# 2022.net
KiCad netlist of a schematic drawn in EAGLE
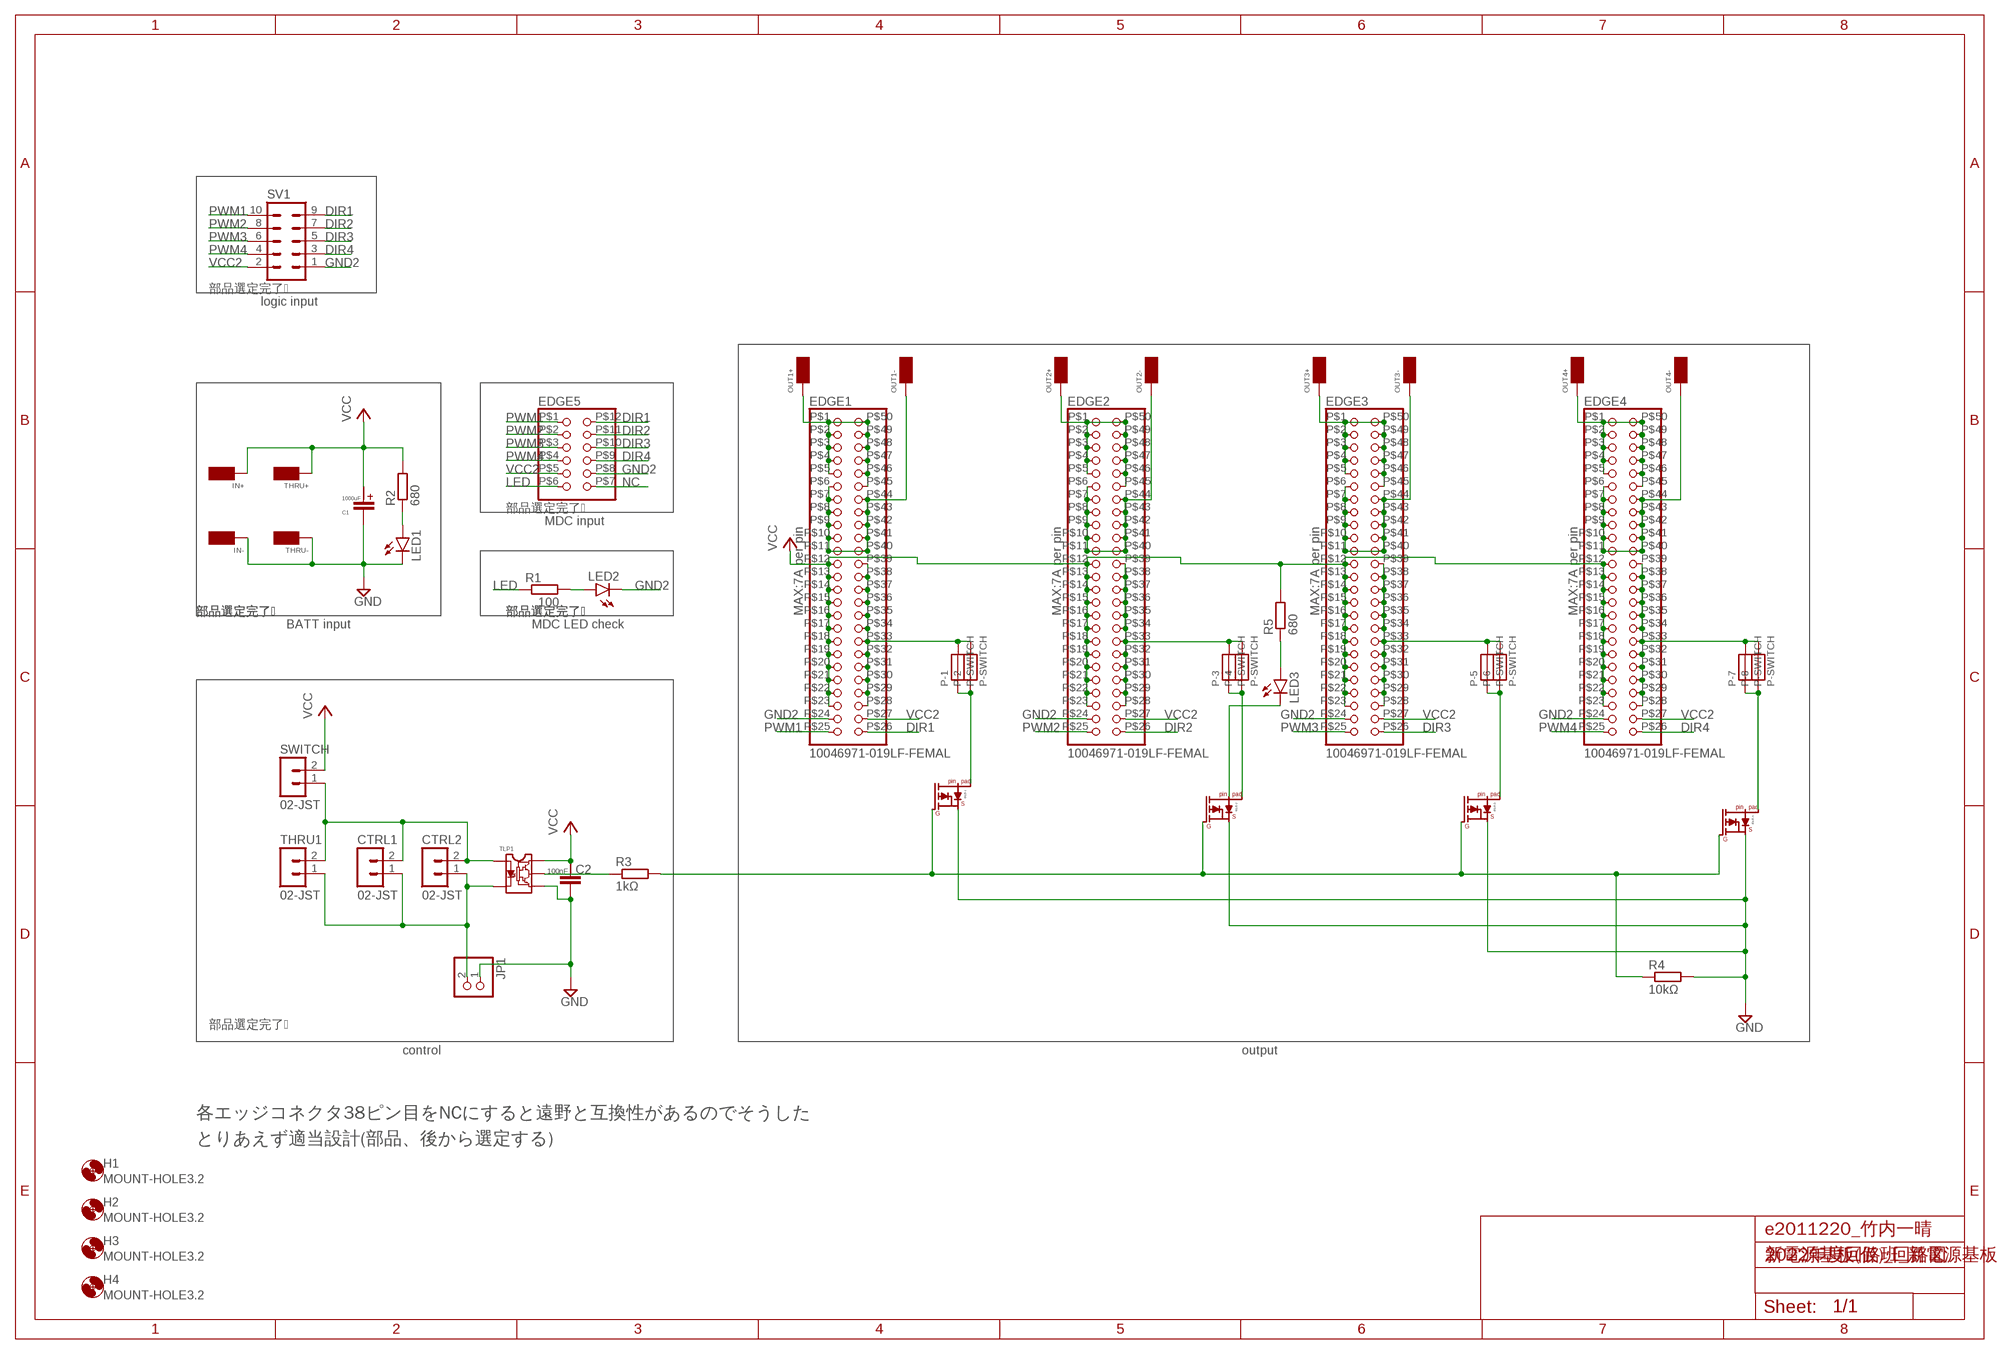
[diagram p0: schematic, sheet 1]

(export (version "E")
  (design (tool "Eeschema 10.0.6"))
  (components
    (comp (ref "C1")
      (value "50ZLH1000MEFC16X25")
      (footprint "eagle-import:50ZLH1000MEFC16X25")
      (libsource (lib "eagle-import") (part "50ZLH1000MEFC16X25"))
    )
    (comp (ref "C2")
      (value "GCM188L81H104KA57")
      (footprint "eagle-import:GCM188L81H104KA57")
      (libsource (lib "eagle-import") (part "GCM188L81H104KA57"))
    )
    (comp (ref "CTRL1")
      (value "02-JST")
      (footprint "eagle-import:B2B-XH")
      (libsource (lib "eagle-import") (part "02-JST"))
    )
    (comp (ref "CTRL2")
      (value "02-JST")
      (footprint "eagle-import:B2B-XH")
      (libsource (lib "eagle-import") (part "02-JST"))
    )
    (comp (ref "EDGE1")
      (value "10046971-019LF-FEMAL")
      (footprint "eagle-import:10046971-019LF")
      (libsource (lib "eagle-import") (part "10046971-019LF-FEMAL"))
    )
    (comp (ref "EDGE2")
      (value "10046971-019LF-FEMAL")
      (footprint "eagle-import:10046971-019LF")
      (libsource (lib "eagle-import") (part "10046971-019LF-FEMAL"))
    )
    (comp (ref "EDGE3")
      (value "10046971-019LF-FEMAL")
      (footprint "eagle-import:10046971-019LF")
      (libsource (lib "eagle-import") (part "10046971-019LF-FEMAL"))
    )
    (comp (ref "EDGE4")
      (value "10046971-019LF-FEMAL")
      (footprint "eagle-import:10046971-019LF")
      (libsource (lib "eagle-import") (part "10046971-019LF-FEMAL"))
    )
    (comp (ref "EDGE5")
      (value "7-5530843-6")
      (footprint "eagle-import:7-5530843-6")
      (libsource (lib "eagle-import") (part "7-5530843-6"))
    )
    (comp (ref "H1")
      (value "MOUNT-HOLE3.2")
      (footprint "eagle-import:3,2")
      (libsource (lib "eagle-import") (part "MOUNT-HOLE3.2"))
    )
    (comp (ref "H2")
      (value "MOUNT-HOLE3.2")
      (footprint "eagle-import:3,2")
      (libsource (lib "eagle-import") (part "MOUNT-HOLE3.2"))
    )
    (comp (ref "H3")
      (value "MOUNT-HOLE3.2")
      (footprint "eagle-import:3,2")
      (libsource (lib "eagle-import") (part "MOUNT-HOLE3.2"))
    )
    (comp (ref "H4")
      (value "MOUNT-HOLE3.2")
      (footprint "eagle-import:3,2")
      (libsource (lib "eagle-import") (part "MOUNT-HOLE3.2"))
    )
    (comp (ref "IN+")
      (value "PADS14")
      (footprint "eagle-import:AWG14")
      (libsource (lib "eagle-import") (part "PADS14"))
    )
    (comp (ref "IN-")
      (value "PADS14")
      (footprint "eagle-import:AWG14")
      (libsource (lib "eagle-import") (part "PADS14"))
    )
    (comp (ref "IRLB-1")
      (value "IRLB3813_2")
      (footprint "eagle-import:TO-220AB-PUT")
      (libsource (lib "eagle-import") (part "IRLB3813_2"))
    )
    (comp (ref "IRLB-2")
      (value "IRLB3813_2")
      (footprint "eagle-import:TO-220AB-PUT")
      (libsource (lib "eagle-import") (part "IRLB3813_2"))
    )
    (comp (ref "IRLB-3")
      (value "IRLB3813_2")
      (footprint "eagle-import:TO-220AB-PUT")
      (libsource (lib "eagle-import") (part "IRLB3813_2"))
    )
    (comp (ref "IRLB-4")
      (value "IRLB3813_2")
      (footprint "eagle-import:TO-220AB-PUT")
      (libsource (lib "eagle-import") (part "IRLB3813_2"))
    )
    (comp (ref "JP1")
      (value "PINHD-1X2")
      (footprint "eagle-import:1X02")
      (libsource (lib "eagle-import") (part "PINHD-1X2"))
    )
    (comp (ref "LED1")
      (value "LED5MM")
      (footprint "eagle-import:LED5MM")
      (libsource (lib "eagle-import") (part "LED5MM"))
    )
    (comp (ref "LED2")
      (value "LED5MM")
      (footprint "eagle-import:LED5MM")
      (libsource (lib "eagle-import") (part "LED5MM"))
    )
    (comp (ref "LED3")
      (value "LED5MM")
      (footprint "eagle-import:LED5MM")
      (libsource (lib "eagle-import") (part "LED5MM"))
    )
    (comp (ref "OUT1+")
      (value "PADS14")
      (footprint "eagle-import:AWG14")
      (libsource (lib "eagle-import") (part "PADS14"))
    )
    (comp (ref "OUT1-")
      (value "PADS14")
      (footprint "eagle-import:AWG14")
      (libsource (lib "eagle-import") (part "PADS14"))
    )
    (comp (ref "OUT2+")
      (value "PADS14")
      (footprint "eagle-import:AWG14")
      (libsource (lib "eagle-import") (part "PADS14"))
    )
    (comp (ref "OUT2-")
      (value "PADS14")
      (footprint "eagle-import:AWG14")
      (libsource (lib "eagle-import") (part "PADS14"))
    )
    (comp (ref "OUT3+")
      (value "PADS14")
      (footprint "eagle-import:AWG14")
      (libsource (lib "eagle-import") (part "PADS14"))
    )
    (comp (ref "OUT3-")
      (value "PADS14")
      (footprint "eagle-import:AWG14")
      (libsource (lib "eagle-import") (part "PADS14"))
    )
    (comp (ref "OUT4+")
      (value "PADS14")
      (footprint "eagle-import:AWG14")
      (libsource (lib "eagle-import") (part "PADS14"))
    )
    (comp (ref "OUT4-")
      (value "PADS14")
      (footprint "eagle-import:AWG14")
      (libsource (lib "eagle-import") (part "PADS14"))
    )
    (comp (ref "P-1")
      (value "P-SWITCH")
      (footprint "eagle-import:P-SWITCH")
      (libsource (lib "eagle-import") (part "P-SWITCH"))
    )
    (comp (ref "P-2")
      (value "P-SWITCH")
      (footprint "eagle-import:P-SWITCH")
      (libsource (lib "eagle-import") (part "P-SWITCH"))
    )
    (comp (ref "P-3")
      (value "P-SWITCH")
      (footprint "eagle-import:P-SWITCH")
      (libsource (lib "eagle-import") (part "P-SWITCH"))
    )
    (comp (ref "P-4")
      (value "P-SWITCH")
      (footprint "eagle-import:P-SWITCH")
      (libsource (lib "eagle-import") (part "P-SWITCH"))
    )
    (comp (ref "P-5")
      (value "P-SWITCH")
      (footprint "eagle-import:P-SWITCH")
      (libsource (lib "eagle-import") (part "P-SWITCH"))
    )
    (comp (ref "P-6")
      (value "P-SWITCH")
      (footprint "eagle-import:P-SWITCH")
      (libsource (lib "eagle-import") (part "P-SWITCH"))
    )
    (comp (ref "P-7")
      (value "P-SWITCH")
      (footprint "eagle-import:P-SWITCH")
      (libsource (lib "eagle-import") (part "P-SWITCH"))
    )
    (comp (ref "P-8")
      (value "P-SWITCH")
      (footprint "eagle-import:P-SWITCH")
      (libsource (lib "eagle-import") (part "P-SWITCH"))
    )
    (comp (ref "R1")
      (value "100")
      (footprint "eagle-import:0204_7")
      (libsource (lib "eagle-import") (part "R-EU_0204/7"))
    )
    (comp (ref "R2")
      (value "680")
      (footprint "eagle-import:0204_7")
      (libsource (lib "eagle-import") (part "R-EU_0204/7"))
    )
    (comp (ref "R3")
      (value "1kΩ")
      (footprint "eagle-import:0204_7")
      (libsource (lib "eagle-import") (part "R-EU_0204/7"))
    )
    (comp (ref "R4")
      (value "10kΩ")
      (footprint "eagle-import:0204_7")
      (libsource (lib "eagle-import") (part "R-EU_0204/7"))
    )
    (comp (ref "R5")
      (value "680")
      (footprint "eagle-import:0204_7")
      (libsource (lib "eagle-import") (part "R-EU_0204/7"))
    )
    (comp (ref "SV1")
      (value "ML10")
      (footprint "eagle-import:ML10")
      (libsource (lib "eagle-import") (part "ML10"))
    )
    (comp (ref "SWITCH")
      (value "02-JST")
      (footprint "eagle-import:B2B-XH")
      (libsource (lib "eagle-import") (part "02-JST"))
    )
    (comp (ref "THRU+")
      (value "PADS14")
      (footprint "eagle-import:AWG14")
      (libsource (lib "eagle-import") (part "PADS14"))
    )
    (comp (ref "THRU-")
      (value "PADS14")
      (footprint "eagle-import:AWG14")
      (libsource (lib "eagle-import") (part "PADS14"))
    )
    (comp (ref "THRU1")
      (value "02-JST")
      (footprint "eagle-import:B2B-XH")
      (libsource (lib "eagle-import") (part "02-JST"))
    )
    (comp (ref "TLP1")
      (value "2227MC-08-03")
      (footprint "eagle-import:2227MC-08-03")
      (libsource (lib "eagle-import") (part "2227MC-08-03"))
    )
  )
  (nets
    (net (code "1") (name "/DIR1") (class "Default")
      (node (ref "EDGE1") (pin "P$26") (pinfunction "P26_P$26") (pintype "passive"))
      (node (ref "EDGE5") (pin "P$12") (pinfunction "P12_P$12") (pintype "passive"))
      (node (ref "SV1") (pin "9") (pinfunction "9_9") (pintype "passive"))
    )
    (net (code "2") (name "/DIR2") (class "Default")
      (node (ref "EDGE2") (pin "P$26") (pinfunction "P26_P$26") (pintype "passive"))
      (node (ref "EDGE5") (pin "P$11") (pinfunction "P11_P$11") (pintype "passive"))
      (node (ref "SV1") (pin "7") (pinfunction "7_7") (pintype "passive"))
    )
    (net (code "3") (name "/DIR3") (class "Default")
      (node (ref "EDGE3") (pin "P$26") (pinfunction "P26_P$26") (pintype "passive"))
      (node (ref "EDGE5") (pin "P$10") (pinfunction "P10_P$10") (pintype "passive"))
      (node (ref "SV1") (pin "5") (pinfunction "5_5") (pintype "passive"))
    )
    (net (code "4") (name "/DIR4") (class "Default")
      (node (ref "EDGE4") (pin "P$26") (pinfunction "P26_P$26") (pintype "passive"))
      (node (ref "EDGE5") (pin "P$9") (pinfunction "P9_P$9") (pintype "passive"))
      (node (ref "SV1") (pin "3") (pinfunction "3_3") (pintype "passive"))
    )
    (net (code "5") (name "/GND2") (class "Default")
      (node (ref "EDGE1") (pin "P$24") (pinfunction "P24_P$24") (pintype "passive"))
      (node (ref "EDGE2") (pin "P$24") (pinfunction "P24_P$24") (pintype "passive"))
      (node (ref "EDGE3") (pin "P$24") (pinfunction "P24_P$24") (pintype "passive"))
      (node (ref "EDGE4") (pin "P$24") (pinfunction "P24_P$24") (pintype "passive"))
      (node (ref "EDGE5") (pin "P$8") (pinfunction "P8_P$8") (pintype "passive"))
      (node (ref "LED2") (pin "K") (pinfunction "C_K") (pintype "passive"))
      (node (ref "SV1") (pin "1") (pinfunction "1_1") (pintype "passive"))
    )
    (net (code "6") (name "/LED") (class "Default")
      (node (ref "EDGE5") (pin "P$6") (pinfunction "P6_P$6") (pintype "passive"))
      (node (ref "R1") (pin "1") (pinfunction "1_1") (pintype "passive"))
    )
    (net (code "7") (name "/NC") (class "Default")
      (node (ref "EDGE5") (pin "P$7") (pinfunction "P7_P$7") (pintype "passive"))
    )
    (net (code "8") (name "/PWM1") (class "Default")
      (node (ref "EDGE1") (pin "P$25") (pinfunction "P25_P$25") (pintype "passive"))
      (node (ref "EDGE5") (pin "P$1") (pinfunction "P1_P$1") (pintype "passive"))
      (node (ref "SV1") (pin "10") (pinfunction "10_10") (pintype "passive"))
    )
    (net (code "9") (name "/PWM2") (class "Default")
      (node (ref "EDGE2") (pin "P$25") (pinfunction "P25_P$25") (pintype "passive"))
      (node (ref "EDGE5") (pin "P$2") (pinfunction "P2_P$2") (pintype "passive"))
      (node (ref "SV1") (pin "8") (pinfunction "8_8") (pintype "passive"))
    )
    (net (code "10") (name "/PWM3") (class "Default")
      (node (ref "EDGE3") (pin "P$25") (pinfunction "P25_P$25") (pintype "passive"))
      (node (ref "EDGE5") (pin "P$3") (pinfunction "P3_P$3") (pintype "passive"))
      (node (ref "SV1") (pin "6") (pinfunction "6_6") (pintype "passive"))
    )
    (net (code "11") (name "/PWM4") (class "Default")
      (node (ref "EDGE4") (pin "P$25") (pinfunction "P25_P$25") (pintype "passive"))
      (node (ref "EDGE5") (pin "P$4") (pinfunction "P4_P$4") (pintype "passive"))
      (node (ref "SV1") (pin "4") (pinfunction "4_4") (pintype "passive"))
    )
    (net (code "12") (name "/VCC2") (class "Default")
      (node (ref "EDGE1") (pin "P$27") (pinfunction "P27_P$27") (pintype "passive"))
      (node (ref "EDGE2") (pin "P$27") (pinfunction "P27_P$27") (pintype "passive"))
      (node (ref "EDGE3") (pin "P$27") (pinfunction "P27_P$27") (pintype "passive"))
      (node (ref "EDGE4") (pin "P$27") (pinfunction "P27_P$27") (pintype "passive"))
      (node (ref "EDGE5") (pin "P$5") (pinfunction "P5_P$5") (pintype "passive"))
      (node (ref "SV1") (pin "2") (pinfunction "2_2") (pintype "passive"))
    )
    (net (code "13") (name "GND") (class "Default")
      (node (ref "C1") (pin "C") (pinfunction "CATHODE_C") (pintype "bidirectional"))
      (node (ref "C2") (pin "P$2") (pinfunction "P$2_P$2") (pintype "bidirectional"))
      (node (ref "IN-") (pin "P$1") (pinfunction "P$1_P$1") (pintype "passive"))
      (node (ref "IRLB-1") (pin "S") (pinfunction "S_S") (pintype "passive"))
      (node (ref "IRLB-2") (pin "S") (pinfunction "S_S") (pintype "passive"))
      (node (ref "IRLB-3") (pin "S") (pinfunction "S_S") (pintype "passive"))
      (node (ref "IRLB-4") (pin "S") (pinfunction "S_S") (pintype "passive"))
      (node (ref "JP1") (pin "1") (pinfunction "1_1") (pintype "passive"))
      (node (ref "LED1") (pin "K") (pinfunction "C_K") (pintype "passive"))
      (node (ref "R4") (pin "2") (pinfunction "2_2") (pintype "passive"))
      (node (ref "THRU-") (pin "P$1") (pinfunction "P$1_P$1") (pintype "passive"))
      (node (ref "TLP1") (pin "P$5") (pinfunction "GND_P$5") (pintype "passive"))
    )
    (net (code "14") (name "Net-(EDGE1-P1)") (class "Default")
      (node (ref "EDGE1") (pin "P$1") (pinfunction "P1_P$1") (pintype "passive"))
      (node (ref "EDGE1") (pin "P$2") (pinfunction "P2_P$2") (pintype "passive"))
      (node (ref "EDGE1") (pin "P$3") (pinfunction "P3_P$3") (pintype "passive"))
      (node (ref "EDGE1") (pin "P$4") (pinfunction "P4_P$4") (pintype "passive"))
      (node (ref "EDGE1") (pin "P$45") (pinfunction "P45_P$45") (pintype "passive"))
      (node (ref "EDGE1") (pin "P$46") (pinfunction "P46_P$46") (pintype "passive"))
      (node (ref "EDGE1") (pin "P$47") (pinfunction "P47_P$47") (pintype "passive"))
      (node (ref "EDGE1") (pin "P$48") (pinfunction "P48_P$48") (pintype "passive"))
      (node (ref "EDGE1") (pin "P$49") (pinfunction "P49_P$49") (pintype "passive"))
      (node (ref "EDGE1") (pin "P$5") (pinfunction "P5_P$5") (pintype "passive"))
      (node (ref "EDGE1") (pin "P$50") (pinfunction "P50_P$50") (pintype "passive"))
      (node (ref "OUT1+") (pin "P$1") (pinfunction "P$1_P$1") (pintype "passive"))
    )
    (net (code "15") (name "Net-(EDGE1-P10)") (class "Default")
      (node (ref "EDGE1") (pin "P$10") (pinfunction "P10_P$10") (pintype "passive"))
      (node (ref "EDGE1") (pin "P$11") (pinfunction "P11_P$11") (pintype "passive"))
      (node (ref "EDGE1") (pin "P$40") (pinfunction "P40_P$40") (pintype "passive"))
      (node (ref "EDGE1") (pin "P$41") (pinfunction "P41_P$41") (pintype "passive"))
      (node (ref "EDGE1") (pin "P$42") (pinfunction "P42_P$42") (pintype "passive"))
      (node (ref "EDGE1") (pin "P$43") (pinfunction "P43_P$43") (pintype "passive"))
      (node (ref "EDGE1") (pin "P$44") (pinfunction "P44_P$44") (pintype "passive"))
      (node (ref "EDGE1") (pin "P$6") (pinfunction "P6_P$6") (pintype "passive"))
      (node (ref "EDGE1") (pin "P$7") (pinfunction "P7_P$7") (pintype "passive"))
      (node (ref "EDGE1") (pin "P$8") (pinfunction "P8_P$8") (pintype "passive"))
      (node (ref "EDGE1") (pin "P$9") (pinfunction "P9_P$9") (pintype "passive"))
      (node (ref "OUT1-") (pin "P$1") (pinfunction "P$1_P$1") (pintype "passive"))
    )
    (net (code "16") (name "Net-(EDGE1-P28)") (class "Default")
      (node (ref "EDGE1") (pin "P$28") (pinfunction "P28_P$28") (pintype "passive"))
      (node (ref "EDGE1") (pin "P$29") (pinfunction "P29_P$29") (pintype "passive"))
      (node (ref "EDGE1") (pin "P$30") (pinfunction "P30_P$30") (pintype "passive"))
      (node (ref "EDGE1") (pin "P$31") (pinfunction "P31_P$31") (pintype "passive"))
      (node (ref "EDGE1") (pin "P$32") (pinfunction "P32_P$32") (pintype "passive"))
      (node (ref "EDGE1") (pin "P$33") (pinfunction "P33_P$33") (pintype "passive"))
      (node (ref "EDGE1") (pin "P$34") (pinfunction "P34_P$34") (pintype "passive"))
      (node (ref "EDGE1") (pin "P$35") (pinfunction "P35_P$35") (pintype "passive"))
      (node (ref "EDGE1") (pin "P$36") (pinfunction "P36_P$36") (pintype "passive"))
      (node (ref "EDGE1") (pin "P$37") (pinfunction "P37_P$37") (pintype "passive"))
      (node (ref "EDGE1") (pin "P$38") (pinfunction "P38_P$38") (pintype "passive"))
      (node (ref "EDGE1") (pin "P$39") (pinfunction "P39_P$39") (pintype "passive"))
      (node (ref "P-1") (pin "P$1") (pinfunction "P$1_P$1") (pintype "passive"))
      (node (ref "P-2") (pin "P$1") (pinfunction "P$1_P$1") (pintype "passive"))
    )
    (net (code "17") (name "Net-(EDGE2-P1)") (class "Default")
      (node (ref "EDGE2") (pin "P$1") (pinfunction "P1_P$1") (pintype "passive"))
      (node (ref "EDGE2") (pin "P$2") (pinfunction "P2_P$2") (pintype "passive"))
      (node (ref "EDGE2") (pin "P$3") (pinfunction "P3_P$3") (pintype "passive"))
      (node (ref "EDGE2") (pin "P$4") (pinfunction "P4_P$4") (pintype "passive"))
      (node (ref "EDGE2") (pin "P$45") (pinfunction "P45_P$45") (pintype "passive"))
      (node (ref "EDGE2") (pin "P$46") (pinfunction "P46_P$46") (pintype "passive"))
      (node (ref "EDGE2") (pin "P$47") (pinfunction "P47_P$47") (pintype "passive"))
      (node (ref "EDGE2") (pin "P$48") (pinfunction "P48_P$48") (pintype "passive"))
      (node (ref "EDGE2") (pin "P$49") (pinfunction "P49_P$49") (pintype "passive"))
      (node (ref "EDGE2") (pin "P$5") (pinfunction "P5_P$5") (pintype "passive"))
      (node (ref "EDGE2") (pin "P$50") (pinfunction "P50_P$50") (pintype "passive"))
      (node (ref "OUT2+") (pin "P$1") (pinfunction "P$1_P$1") (pintype "passive"))
    )
    (net (code "18") (name "Net-(EDGE2-P10)") (class "Default")
      (node (ref "EDGE2") (pin "P$10") (pinfunction "P10_P$10") (pintype "passive"))
      (node (ref "EDGE2") (pin "P$11") (pinfunction "P11_P$11") (pintype "passive"))
      (node (ref "EDGE2") (pin "P$40") (pinfunction "P40_P$40") (pintype "passive"))
      (node (ref "EDGE2") (pin "P$41") (pinfunction "P41_P$41") (pintype "passive"))
      (node (ref "EDGE2") (pin "P$42") (pinfunction "P42_P$42") (pintype "passive"))
      (node (ref "EDGE2") (pin "P$43") (pinfunction "P43_P$43") (pintype "passive"))
      (node (ref "EDGE2") (pin "P$44") (pinfunction "P44_P$44") (pintype "passive"))
      (node (ref "EDGE2") (pin "P$6") (pinfunction "P6_P$6") (pintype "passive"))
      (node (ref "EDGE2") (pin "P$7") (pinfunction "P7_P$7") (pintype "passive"))
      (node (ref "EDGE2") (pin "P$8") (pinfunction "P8_P$8") (pintype "passive"))
      (node (ref "EDGE2") (pin "P$9") (pinfunction "P9_P$9") (pintype "passive"))
      (node (ref "OUT2-") (pin "P$1") (pinfunction "P$1_P$1") (pintype "passive"))
    )
    (net (code "19") (name "Net-(EDGE2-P28)") (class "Default")
      (node (ref "EDGE2") (pin "P$28") (pinfunction "P28_P$28") (pintype "passive"))
      (node (ref "EDGE2") (pin "P$29") (pinfunction "P29_P$29") (pintype "passive"))
      (node (ref "EDGE2") (pin "P$30") (pinfunction "P30_P$30") (pintype "passive"))
      (node (ref "EDGE2") (pin "P$31") (pinfunction "P31_P$31") (pintype "passive"))
      (node (ref "EDGE2") (pin "P$32") (pinfunction "P32_P$32") (pintype "passive"))
      (node (ref "EDGE2") (pin "P$33") (pinfunction "P33_P$33") (pintype "passive"))
      (node (ref "EDGE2") (pin "P$34") (pinfunction "P34_P$34") (pintype "passive"))
      (node (ref "EDGE2") (pin "P$35") (pinfunction "P35_P$35") (pintype "passive"))
      (node (ref "EDGE2") (pin "P$36") (pinfunction "P36_P$36") (pintype "passive"))
      (node (ref "EDGE2") (pin "P$37") (pinfunction "P37_P$37") (pintype "passive"))
      (node (ref "EDGE2") (pin "P$38") (pinfunction "P38_P$38") (pintype "passive"))
      (node (ref "EDGE2") (pin "P$39") (pinfunction "P39_P$39") (pintype "passive"))
      (node (ref "P-3") (pin "P$1") (pinfunction "P$1_P$1") (pintype "passive"))
      (node (ref "P-4") (pin "P$1") (pinfunction "P$1_P$1") (pintype "passive"))
    )
    (net (code "20") (name "Net-(EDGE3-P1)") (class "Default")
      (node (ref "EDGE3") (pin "P$1") (pinfunction "P1_P$1") (pintype "passive"))
      (node (ref "EDGE3") (pin "P$2") (pinfunction "P2_P$2") (pintype "passive"))
      (node (ref "EDGE3") (pin "P$3") (pinfunction "P3_P$3") (pintype "passive"))
      (node (ref "EDGE3") (pin "P$4") (pinfunction "P4_P$4") (pintype "passive"))
      (node (ref "EDGE3") (pin "P$45") (pinfunction "P45_P$45") (pintype "passive"))
      (node (ref "EDGE3") (pin "P$46") (pinfunction "P46_P$46") (pintype "passive"))
      (node (ref "EDGE3") (pin "P$47") (pinfunction "P47_P$47") (pintype "passive"))
      (node (ref "EDGE3") (pin "P$48") (pinfunction "P48_P$48") (pintype "passive"))
      (node (ref "EDGE3") (pin "P$49") (pinfunction "P49_P$49") (pintype "passive"))
      (node (ref "EDGE3") (pin "P$5") (pinfunction "P5_P$5") (pintype "passive"))
      (node (ref "EDGE3") (pin "P$50") (pinfunction "P50_P$50") (pintype "passive"))
      (node (ref "OUT3+") (pin "P$1") (pinfunction "P$1_P$1") (pintype "passive"))
    )
    (net (code "21") (name "Net-(EDGE3-P10)") (class "Default")
      (node (ref "EDGE3") (pin "P$10") (pinfunction "P10_P$10") (pintype "passive"))
      (node (ref "EDGE3") (pin "P$11") (pinfunction "P11_P$11") (pintype "passive"))
      (node (ref "EDGE3") (pin "P$40") (pinfunction "P40_P$40") (pintype "passive"))
      (node (ref "EDGE3") (pin "P$41") (pinfunction "P41_P$41") (pintype "passive"))
      (node (ref "EDGE3") (pin "P$42") (pinfunction "P42_P$42") (pintype "passive"))
      (node (ref "EDGE3") (pin "P$43") (pinfunction "P43_P$43") (pintype "passive"))
      (node (ref "EDGE3") (pin "P$44") (pinfunction "P44_P$44") (pintype "passive"))
      (node (ref "EDGE3") (pin "P$6") (pinfunction "P6_P$6") (pintype "passive"))
      (node (ref "EDGE3") (pin "P$7") (pinfunction "P7_P$7") (pintype "passive"))
      (node (ref "EDGE3") (pin "P$8") (pinfunction "P8_P$8") (pintype "passive"))
      (node (ref "EDGE3") (pin "P$9") (pinfunction "P9_P$9") (pintype "passive"))
      (node (ref "OUT3-") (pin "P$1") (pinfunction "P$1_P$1") (pintype "passive"))
    )
    (net (code "22") (name "Net-(EDGE3-P28)") (class "Default")
      (node (ref "EDGE3") (pin "P$28") (pinfunction "P28_P$28") (pintype "passive"))
      (node (ref "EDGE3") (pin "P$29") (pinfunction "P29_P$29") (pintype "passive"))
      (node (ref "EDGE3") (pin "P$30") (pinfunction "P30_P$30") (pintype "passive"))
      (node (ref "EDGE3") (pin "P$31") (pinfunction "P31_P$31") (pintype "passive"))
      (node (ref "EDGE3") (pin "P$32") (pinfunction "P32_P$32") (pintype "passive"))
      (node (ref "EDGE3") (pin "P$33") (pinfunction "P33_P$33") (pintype "passive"))
      (node (ref "EDGE3") (pin "P$34") (pinfunction "P34_P$34") (pintype "passive"))
      (node (ref "EDGE3") (pin "P$35") (pinfunction "P35_P$35") (pintype "passive"))
      (node (ref "EDGE3") (pin "P$36") (pinfunction "P36_P$36") (pintype "passive"))
      (node (ref "EDGE3") (pin "P$37") (pinfunction "P37_P$37") (pintype "passive"))
      (node (ref "EDGE3") (pin "P$38") (pinfunction "P38_P$38") (pintype "passive"))
      (node (ref "EDGE3") (pin "P$39") (pinfunction "P39_P$39") (pintype "passive"))
      (node (ref "P-5") (pin "P$1") (pinfunction "P$1_P$1") (pintype "passive"))
      (node (ref "P-6") (pin "P$1") (pinfunction "P$1_P$1") (pintype "passive"))
    )
    (net (code "23") (name "Net-(EDGE4-P1)") (class "Default")
      (node (ref "EDGE4") (pin "P$1") (pinfunction "P1_P$1") (pintype "passive"))
      (node (ref "EDGE4") (pin "P$2") (pinfunction "P2_P$2") (pintype "passive"))
      (node (ref "EDGE4") (pin "P$3") (pinfunction "P3_P$3") (pintype "passive"))
      (node (ref "EDGE4") (pin "P$4") (pinfunction "P4_P$4") (pintype "passive"))
      (node (ref "EDGE4") (pin "P$45") (pinfunction "P45_P$45") (pintype "passive"))
      (node (ref "EDGE4") (pin "P$46") (pinfunction "P46_P$46") (pintype "passive"))
      (node (ref "EDGE4") (pin "P$47") (pinfunction "P47_P$47") (pintype "passive"))
      (node (ref "EDGE4") (pin "P$48") (pinfunction "P48_P$48") (pintype "passive"))
      (node (ref "EDGE4") (pin "P$49") (pinfunction "P49_P$49") (pintype "passive"))
      (node (ref "EDGE4") (pin "P$5") (pinfunction "P5_P$5") (pintype "passive"))
      (node (ref "EDGE4") (pin "P$50") (pinfunction "P50_P$50") (pintype "passive"))
      (node (ref "OUT4+") (pin "P$1") (pinfunction "P$1_P$1") (pintype "passive"))
    )
    (net (code "24") (name "Net-(EDGE4-P10)") (class "Default")
      (node (ref "EDGE4") (pin "P$10") (pinfunction "P10_P$10") (pintype "passive"))
      (node (ref "EDGE4") (pin "P$11") (pinfunction "P11_P$11") (pintype "passive"))
      (node (ref "EDGE4") (pin "P$40") (pinfunction "P40_P$40") (pintype "passive"))
      (node (ref "EDGE4") (pin "P$41") (pinfunction "P41_P$41") (pintype "passive"))
      (node (ref "EDGE4") (pin "P$42") (pinfunction "P42_P$42") (pintype "passive"))
      (node (ref "EDGE4") (pin "P$43") (pinfunction "P43_P$43") (pintype "passive"))
      (node (ref "EDGE4") (pin "P$44") (pinfunction "P44_P$44") (pintype "passive"))
      (node (ref "EDGE4") (pin "P$6") (pinfunction "P6_P$6") (pintype "passive"))
      (node (ref "EDGE4") (pin "P$7") (pinfunction "P7_P$7") (pintype "passive"))
      (node (ref "EDGE4") (pin "P$8") (pinfunction "P8_P$8") (pintype "passive"))
      (node (ref "EDGE4") (pin "P$9") (pinfunction "P9_P$9") (pintype "passive"))
      (node (ref "OUT4-") (pin "P$1") (pinfunction "P$1_P$1") (pintype "passive"))
    )
    (net (code "25") (name "Net-(EDGE4-P28)") (class "Default")
      (node (ref "EDGE4") (pin "P$28") (pinfunction "P28_P$28") (pintype "passive"))
      (node (ref "EDGE4") (pin "P$29") (pinfunction "P29_P$29") (pintype "passive"))
      (node (ref "EDGE4") (pin "P$30") (pinfunction "P30_P$30") (pintype "passive"))
      (node (ref "EDGE4") (pin "P$31") (pinfunction "P31_P$31") (pintype "passive"))
      (node (ref "EDGE4") (pin "P$32") (pinfunction "P32_P$32") (pintype "passive"))
      (node (ref "EDGE4") (pin "P$33") (pinfunction "P33_P$33") (pintype "passive"))
      (node (ref "EDGE4") (pin "P$34") (pinfunction "P34_P$34") (pintype "passive"))
      (node (ref "EDGE4") (pin "P$35") (pinfunction "P35_P$35") (pintype "passive"))
      (node (ref "EDGE4") (pin "P$36") (pinfunction "P36_P$36") (pintype "passive"))
      (node (ref "EDGE4") (pin "P$37") (pinfunction "P37_P$37") (pintype "passive"))
      (node (ref "EDGE4") (pin "P$38") (pinfunction "P38_P$38") (pintype "passive"))
      (node (ref "EDGE4") (pin "P$39") (pinfunction "P39_P$39") (pintype "passive"))
      (node (ref "P-7") (pin "P$1") (pinfunction "P$1_P$1") (pintype "passive"))
      (node (ref "P-8") (pin "P$1") (pinfunction "P$1_P$1") (pintype "passive"))
    )
    (net (code "26") (name "Net-(IRLB-1-PD)") (class "Default")
      (node (ref "IRLB-1") (pin "P$1") (pinfunction "PD_P$1") (pintype "passive"))
      (node (ref "P-1") (pin "P$2") (pinfunction "P$2_P$2") (pintype "passive"))
      (node (ref "P-2") (pin "P$2") (pinfunction "P$2_P$2") (pintype "passive"))
    )
    (net (code "27") (name "Net-(IRLB-1-PadG)") (class "Default")
      (node (ref "IRLB-1") (pin "G") (pinfunction "G_G") (pintype "passive"))
      (node (ref "IRLB-2") (pin "G") (pinfunction "G_G") (pintype "passive"))
      (node (ref "IRLB-3") (pin "G") (pinfunction "G_G") (pintype "passive"))
      (node (ref "IRLB-4") (pin "G") (pinfunction "G_G") (pintype "passive"))
      (node (ref "R3") (pin "2") (pinfunction "2_2") (pintype "passive"))
      (node (ref "R4") (pin "1") (pinfunction "1_1") (pintype "passive"))
    )
    (net (code "28") (name "Net-(IRLB-2-PD)") (class "Default")
      (node (ref "IRLB-2") (pin "P$1") (pinfunction "PD_P$1") (pintype "passive"))
      (node (ref "P-3") (pin "P$2") (pinfunction "P$2_P$2") (pintype "passive"))
      (node (ref "P-4") (pin "P$2") (pinfunction "P$2_P$2") (pintype "passive"))
    )
    (net (code "29") (name "Net-(IRLB-3-PD)") (class "Default")
      (node (ref "IRLB-3") (pin "P$1") (pinfunction "PD_P$1") (pintype "passive"))
      (node (ref "P-5") (pin "P$2") (pinfunction "P$2_P$2") (pintype "passive"))
      (node (ref "P-6") (pin "P$2") (pinfunction "P$2_P$2") (pintype "passive"))
    )
    (net (code "30") (name "Net-(IRLB-4-PD)") (class "Default")
      (node (ref "IRLB-4") (pin "P$1") (pinfunction "PD_P$1") (pintype "passive"))
      (node (ref "P-7") (pin "P$2") (pinfunction "P$2_P$2") (pintype "passive"))
      (node (ref "P-8") (pin "P$2") (pinfunction "P$2_P$2") (pintype "passive"))
    )
    (net (code "31") (name "Net-(LED1-PadA)") (class "Default")
      (node (ref "LED1") (pin "A") (pinfunction "A_A") (pintype "passive"))
      (node (ref "R2") (pin "1") (pinfunction "1_1") (pintype "passive"))
    )
    (net (code "32") (name "Net-(LED2-PadA)") (class "Default")
      (node (ref "LED2") (pin "A") (pinfunction "A_A") (pintype "passive"))
      (node (ref "R1") (pin "2") (pinfunction "2_2") (pintype "passive"))
    )
    (net (code "33") (name "Net-(LED3-C)") (class "Default")
      (node (ref "IRLB-2") (pin "D") (pinfunction "D_D") (pintype "passive"))
      (node (ref "LED3") (pin "K") (pinfunction "C_K") (pintype "passive"))
    )
    (net (code "34") (name "Net-(LED3-PadA)") (class "Default")
      (node (ref "LED3") (pin "A") (pinfunction "A_A") (pintype "passive"))
      (node (ref "R5") (pin "1") (pinfunction "1_1") (pintype "passive"))
    )
    (net (code "35") (name "Net-(TLP1-ANODE)") (class "Default")
      (node (ref "CTRL1") (pin "2") (pinfunction "2_2") (pintype "passive"))
      (node (ref "CTRL2") (pin "2") (pinfunction "2_2") (pintype "passive"))
      (node (ref "SWITCH") (pin "1") (pinfunction "1_1") (pintype "passive"))
      (node (ref "THRU1") (pin "2") (pinfunction "2_2") (pintype "passive"))
      (node (ref "TLP1") (pin "P$2") (pinfunction "ANODE_P$2") (pintype "passive"))
    )
    (net (code "36") (name "Net-(TLP1-CATHODE)") (class "Default")
      (node (ref "CTRL1") (pin "1") (pinfunction "1_1") (pintype "passive"))
      (node (ref "CTRL2") (pin "1") (pinfunction "1_1") (pintype "passive"))
      (node (ref "JP1") (pin "2") (pinfunction "2_2") (pintype "passive"))
      (node (ref "THRU1") (pin "1") (pinfunction "1_1") (pintype "passive"))
      (node (ref "TLP1") (pin "P$3") (pinfunction "CATHODE_P$3") (pintype "passive"))
    )
    (net (code "37") (name "Net-(TLP1-VOUT)") (class "Default")
      (node (ref "R3") (pin "1") (pinfunction "1_1") (pintype "passive"))
      (node (ref "TLP1") (pin "P$6") (pinfunction "VOUT_P$6") (pintype "passive"))
    )
    (net (code "38") (name "VCC") (class "Default")
      (node (ref "C1") (pin "A") (pinfunction "ANODE_A") (pintype "bidirectional"))
      (node (ref "C2") (pin "P$1") (pinfunction "P$1_P$1") (pintype "bidirectional"))
      (node (ref "EDGE1") (pin "P$12") (pinfunction "P12_P$12") (pintype "passive"))
      (node (ref "EDGE1") (pin "P$13") (pinfunction "P13_P$13") (pintype "passive"))
      (node (ref "EDGE1") (pin "P$14") (pinfunction "P14_P$14") (pintype "passive"))
      (node (ref "EDGE1") (pin "P$15") (pinfunction "P15_P$15") (pintype "passive"))
      (node (ref "EDGE1") (pin "P$16") (pinfunction "P16_P$16") (pintype "passive"))
      (node (ref "EDGE1") (pin "P$17") (pinfunction "P17_P$17") (pintype "passive"))
      (node (ref "EDGE1") (pin "P$18") (pinfunction "P18_P$18") (pintype "passive"))
      (node (ref "EDGE1") (pin "P$19") (pinfunction "P19_P$19") (pintype "passive"))
      (node (ref "EDGE1") (pin "P$20") (pinfunction "P20_P$20") (pintype "passive"))
      (node (ref "EDGE1") (pin "P$21") (pinfunction "P21_P$21") (pintype "passive"))
      (node (ref "EDGE1") (pin "P$22") (pinfunction "P22_P$22") (pintype "passive"))
      (node (ref "EDGE1") (pin "P$23") (pinfunction "P23_P$23") (pintype "passive"))
      (node (ref "EDGE2") (pin "P$12") (pinfunction "P12_P$12") (pintype "passive"))
      (node (ref "EDGE2") (pin "P$13") (pinfunction "P13_P$13") (pintype "passive"))
      (node (ref "EDGE2") (pin "P$14") (pinfunction "P14_P$14") (pintype "passive"))
      (node (ref "EDGE2") (pin "P$15") (pinfunction "P15_P$15") (pintype "passive"))
      (node (ref "EDGE2") (pin "P$16") (pinfunction "P16_P$16") (pintype "passive"))
      (node (ref "EDGE2") (pin "P$17") (pinfunction "P17_P$17") (pintype "passive"))
      (node (ref "EDGE2") (pin "P$18") (pinfunction "P18_P$18") (pintype "passive"))
      (node (ref "EDGE2") (pin "P$19") (pinfunction "P19_P$19") (pintype "passive"))
      (node (ref "EDGE2") (pin "P$20") (pinfunction "P20_P$20") (pintype "passive"))
      (node (ref "EDGE2") (pin "P$21") (pinfunction "P21_P$21") (pintype "passive"))
      (node (ref "EDGE2") (pin "P$22") (pinfunction "P22_P$22") (pintype "passive"))
      (node (ref "EDGE2") (pin "P$23") (pinfunction "P23_P$23") (pintype "passive"))
      (node (ref "EDGE3") (pin "P$12") (pinfunction "P12_P$12") (pintype "passive"))
      (node (ref "EDGE3") (pin "P$13") (pinfunction "P13_P$13") (pintype "passive"))
      (node (ref "EDGE3") (pin "P$14") (pinfunction "P14_P$14") (pintype "passive"))
      (node (ref "EDGE3") (pin "P$15") (pinfunction "P15_P$15") (pintype "passive"))
      (node (ref "EDGE3") (pin "P$16") (pinfunction "P16_P$16") (pintype "passive"))
      (node (ref "EDGE3") (pin "P$17") (pinfunction "P17_P$17") (pintype "passive"))
      (node (ref "EDGE3") (pin "P$18") (pinfunction "P18_P$18") (pintype "passive"))
      (node (ref "EDGE3") (pin "P$19") (pinfunction "P19_P$19") (pintype "passive"))
      (node (ref "EDGE3") (pin "P$20") (pinfunction "P20_P$20") (pintype "passive"))
      (node (ref "EDGE3") (pin "P$21") (pinfunction "P21_P$21") (pintype "passive"))
      (node (ref "EDGE3") (pin "P$22") (pinfunction "P22_P$22") (pintype "passive"))
      (node (ref "EDGE3") (pin "P$23") (pinfunction "P23_P$23") (pintype "passive"))
      (node (ref "EDGE4") (pin "P$12") (pinfunction "P12_P$12") (pintype "passive"))
      (node (ref "EDGE4") (pin "P$13") (pinfunction "P13_P$13") (pintype "passive"))
      (node (ref "EDGE4") (pin "P$14") (pinfunction "P14_P$14") (pintype "passive"))
      (node (ref "EDGE4") (pin "P$15") (pinfunction "P15_P$15") (pintype "passive"))
      (node (ref "EDGE4") (pin "P$16") (pinfunction "P16_P$16") (pintype "passive"))
      (node (ref "EDGE4") (pin "P$17") (pinfunction "P17_P$17") (pintype "passive"))
      (node (ref "EDGE4") (pin "P$18") (pinfunction "P18_P$18") (pintype "passive"))
      (node (ref "EDGE4") (pin "P$19") (pinfunction "P19_P$19") (pintype "passive"))
      (node (ref "EDGE4") (pin "P$20") (pinfunction "P20_P$20") (pintype "passive"))
      (node (ref "EDGE4") (pin "P$21") (pinfunction "P21_P$21") (pintype "passive"))
      (node (ref "EDGE4") (pin "P$22") (pinfunction "P22_P$22") (pintype "passive"))
      (node (ref "EDGE4") (pin "P$23") (pinfunction "P23_P$23") (pintype "passive"))
      (node (ref "IN+") (pin "P$1") (pinfunction "P$1_P$1") (pintype "passive"))
      (node (ref "R2") (pin "2") (pinfunction "2_2") (pintype "passive"))
      (node (ref "R5") (pin "2") (pinfunction "2_2") (pintype "passive"))
      (node (ref "SWITCH") (pin "2") (pinfunction "2_2") (pintype "passive"))
      (node (ref "THRU+") (pin "P$1") (pinfunction "P$1_P$1") (pintype "passive"))
      (node (ref "TLP1") (pin "P$8") (pinfunction "VCC_P$8") (pintype "passive"))
    )
    (net (code "39") (name "unconnected-(IRLB-1-PadD)") (class "Default")
      (node (ref "IRLB-1") (pin "D") (pinfunction "D_D") (pintype "passive"))
    )
    (net (code "40") (name "unconnected-(IRLB-3-PadD)") (class "Default")
      (node (ref "IRLB-3") (pin "D") (pinfunction "D_D") (pintype "passive"))
    )
    (net (code "41") (name "unconnected-(IRLB-4-PadD)") (class "Default")
      (node (ref "IRLB-4") (pin "D") (pinfunction "D_D") (pintype "passive"))
    )
  )
)
